# science_pcb_urc_v1.net
KiCad netlist of a schematic drawn in EAGLE
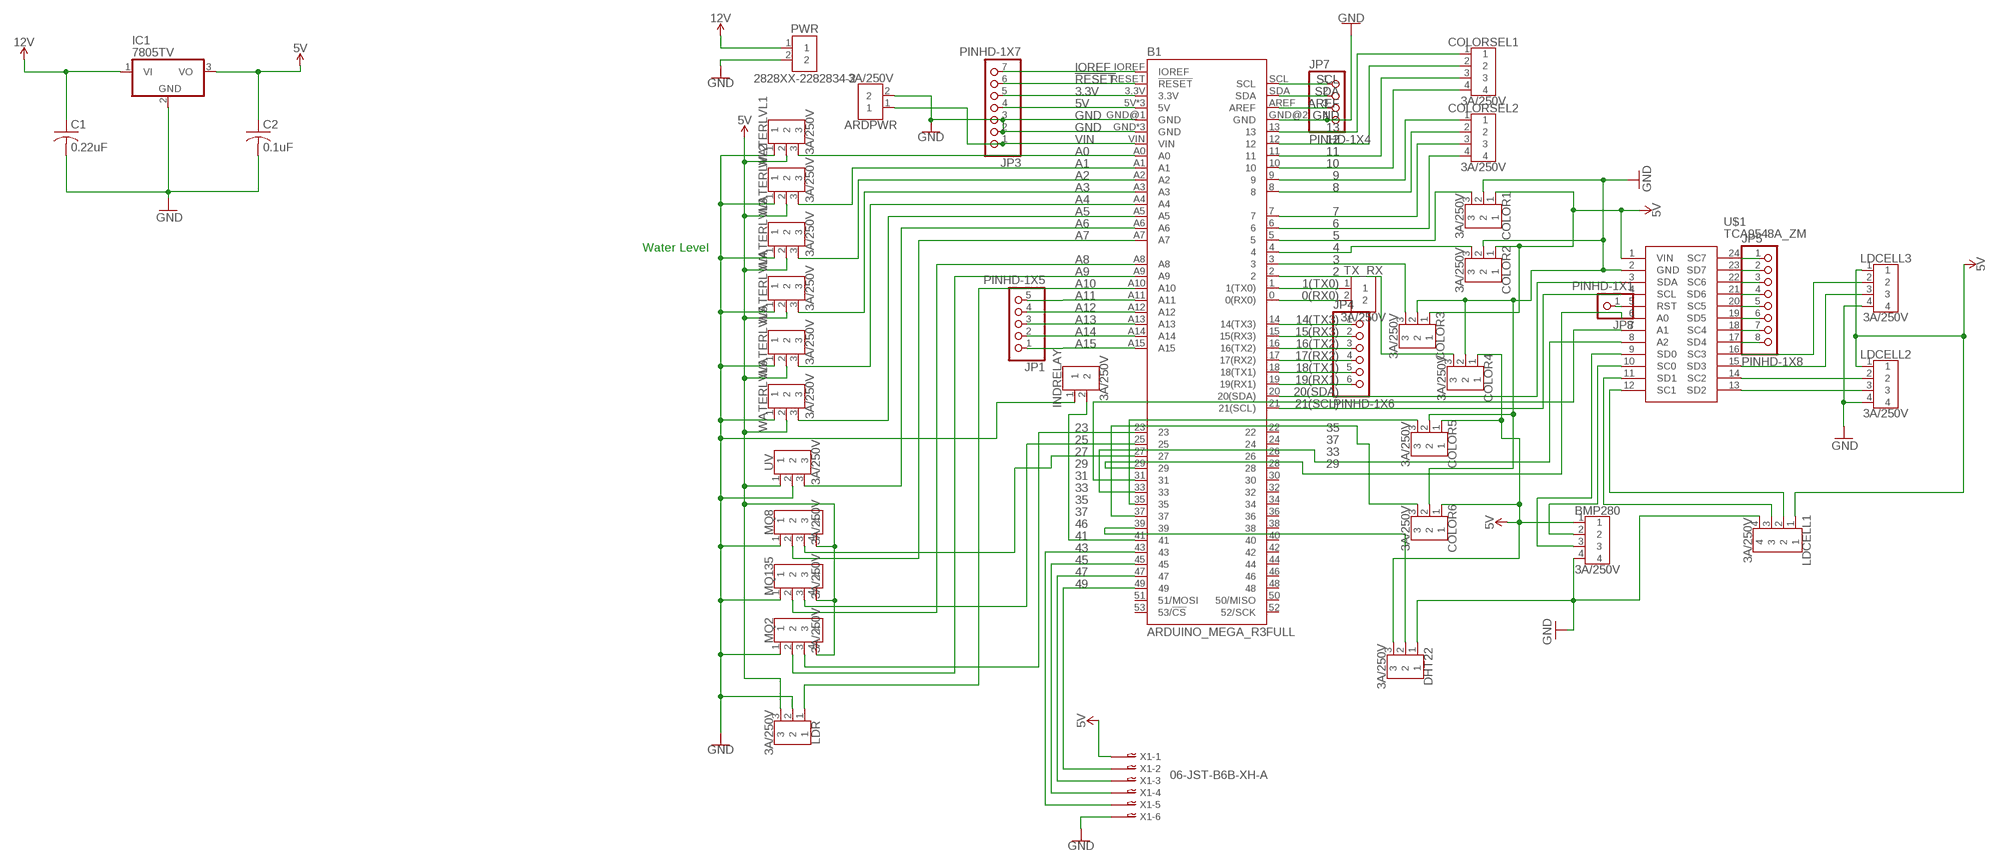
[diagram p0: schematic, sheet 1]

(export (version "E")
  (design (tool "Eeschema 10.0.6"))
  (components
    (comp (ref "ARDPWR")
      (value "3A/250V")
      (footprint "eagle-import:B2B-XH-A")
      (fields (field (name "MANUFACTURER") "JST (XH CONNECTOR)") (field (name "MPN") "B2B-XH-A"))
      (libsource (lib "eagle-import") (part "B2B-XH-A"))
    )
    (comp (ref "B1")
      (value "ARDUINO_MEGA_R3FULL")
      (footprint "eagle-import:ARDUINO_MEGA_NO_SILK")
      (libsource (lib "eagle-import") (part "ARDUINO_MEGA_R3FULL"))
    )
    (comp (ref "BMP280")
      (value "3A/250V")
      (footprint "eagle-import:B4B-XH-A")
      (fields (field (name "MANUFACTURER") "JST (XH connector)") (field (name "MPN") "B4B-XH-A"))
      (libsource (lib "eagle-import") (part "B4B-XH-A"))
    )
    (comp (ref "C1")
      (value "0.22uF")
      (footprint "eagle-import:C025-025X050")
      (libsource (lib "eagle-import") (part "C-US025-025X050"))
    )
    (comp (ref "C2")
      (value "0.1uF")
      (footprint "eagle-import:C025-025X050")
      (libsource (lib "eagle-import") (part "C-US025-025X050"))
    )
    (comp (ref "COLOR1")
      (value "3A/250V")
      (footprint "eagle-import:B3B-XH-A")
      (fields (field (name "MANUFACTURER") "JST (XH connector)") (field (name "MPN") "B3B-XH-A"))
      (libsource (lib "eagle-import") (part "B3B-XH-A"))
    )
    (comp (ref "COLOR2")
      (value "3A/250V")
      (footprint "eagle-import:B3B-XH-A")
      (fields (field (name "MANUFACTURER") "JST (XH connector)") (field (name "MPN") "B3B-XH-A"))
      (libsource (lib "eagle-import") (part "B3B-XH-A"))
    )
    (comp (ref "COLOR3")
      (value "3A/250V")
      (footprint "eagle-import:B3B-XH-A")
      (fields (field (name "MANUFACTURER") "JST (XH connector)") (field (name "MPN") "B3B-XH-A"))
      (libsource (lib "eagle-import") (part "B3B-XH-A"))
    )
    (comp (ref "COLOR4")
      (value "3A/250V")
      (footprint "eagle-import:B3B-XH-A")
      (fields (field (name "MANUFACTURER") "JST (XH connector)") (field (name "MPN") "B3B-XH-A"))
      (libsource (lib "eagle-import") (part "B3B-XH-A"))
    )
    (comp (ref "COLOR5")
      (value "3A/250V")
      (footprint "eagle-import:B3B-XH-A")
      (fields (field (name "MANUFACTURER") "JST (XH connector)") (field (name "MPN") "B3B-XH-A"))
      (libsource (lib "eagle-import") (part "B3B-XH-A"))
    )
    (comp (ref "COLOR6")
      (value "3A/250V")
      (footprint "eagle-import:B3B-XH-A")
      (fields (field (name "MANUFACTURER") "JST (XH connector)") (field (name "MPN") "B3B-XH-A"))
      (libsource (lib "eagle-import") (part "B3B-XH-A"))
    )
    (comp (ref "COLORSEL1")
      (value "3A/250V")
      (footprint "eagle-import:B4B-XH-A")
      (fields (field (name "MANUFACTURER") "JST (XH connector)") (field (name "MPN") "B4B-XH-A"))
      (libsource (lib "eagle-import") (part "B4B-XH-A"))
    )
    (comp (ref "COLORSEL2")
      (value "3A/250V")
      (footprint "eagle-import:B4B-XH-A")
      (fields (field (name "MANUFACTURER") "JST (XH connector)") (field (name "MPN") "B4B-XH-A"))
      (libsource (lib "eagle-import") (part "B4B-XH-A"))
    )
    (comp (ref "DHT22")
      (value "3A/250V")
      (footprint "eagle-import:B3B-XH-A")
      (fields (field (name "MANUFACTURER") "JST (XH connector)") (field (name "MPN") "B3B-XH-A"))
      (libsource (lib "eagle-import") (part "B3B-XH-A"))
    )
    (comp (ref "IC1")
      (value "7805TV")
      (footprint "eagle-import:TO220V")
      (libsource (lib "eagle-import") (part "78TV05"))
    )
    (comp (ref "INDRELAY")
      (value "3A/250V")
      (footprint "eagle-import:B2B-XH-A")
      (fields (field (name "MANUFACTURER") "JST (XH CONNECTOR)") (field (name "MPN") "B2B-XH-A"))
      (libsource (lib "eagle-import") (part "B2B-XH-A"))
    )
    (comp (ref "JP1")
      (value "PINHD-1X5")
      (footprint "eagle-import:1X05")
      (libsource (lib "eagle-import") (part "PINHD-1X5"))
    )
    (comp (ref "JP3")
      (value "PINHD-1X7")
      (footprint "eagle-import:1X07")
      (libsource (lib "eagle-import") (part "PINHD-1X7"))
    )
    (comp (ref "JP4")
      (value "PINHD-1X6")
      (footprint "eagle-import:1X06")
      (libsource (lib "eagle-import") (part "PINHD-1X6"))
    )
    (comp (ref "JP5")
      (value "PINHD-1X8")
      (footprint "eagle-import:1X08")
      (libsource (lib "eagle-import") (part "PINHD-1X8"))
    )
    (comp (ref "JP7")
      (value "PINHD-1X4")
      (footprint "eagle-import:1X04")
      (libsource (lib "eagle-import") (part "PINHD-1X4"))
    )
    (comp (ref "JP8")
      (value "PINHD-1X1")
      (footprint "eagle-import:1X01")
      (libsource (lib "eagle-import") (part "PINHD-1X1"))
    )
    (comp (ref "LDCELL1")
      (value "3A/250V")
      (footprint "eagle-import:B4B-XH-A")
      (fields (field (name "MANUFACTURER") "JST (XH connector)") (field (name "MPN") "B4B-XH-A"))
      (libsource (lib "eagle-import") (part "B4B-XH-A"))
    )
    (comp (ref "LDCELL2")
      (value "3A/250V")
      (footprint "eagle-import:B4B-XH-A")
      (fields (field (name "MANUFACTURER") "JST (XH connector)") (field (name "MPN") "B4B-XH-A"))
      (libsource (lib "eagle-import") (part "B4B-XH-A"))
    )
    (comp (ref "LDCELL3")
      (value "3A/250V")
      (footprint "eagle-import:B4B-XH-A")
      (fields (field (name "MANUFACTURER") "JST (XH connector)") (field (name "MPN") "B4B-XH-A"))
      (libsource (lib "eagle-import") (part "B4B-XH-A"))
    )
    (comp (ref "LDR")
      (value "3A/250V")
      (footprint "eagle-import:B3B-XH-A")
      (fields (field (name "MANUFACTURER") "JST (XH connector)") (field (name "MPN") "B3B-XH-A"))
      (libsource (lib "eagle-import") (part "B3B-XH-A"))
    )
    (comp (ref "MQ2")
      (value "3A/250V")
      (footprint "eagle-import:B4B-XH-A")
      (fields (field (name "MANUFACTURER") "JST (XH connector)") (field (name "MPN") "B4B-XH-A"))
      (libsource (lib "eagle-import") (part "B4B-XH-A"))
    )
    (comp (ref "MQ8")
      (value "3A/250V")
      (footprint "eagle-import:B4B-XH-A")
      (fields (field (name "MANUFACTURER") "JST (XH connector)") (field (name "MPN") "B4B-XH-A"))
      (libsource (lib "eagle-import") (part "B4B-XH-A"))
    )
    (comp (ref "MQ135")
      (value "3A/250V")
      (footprint "eagle-import:B4B-XH-A")
      (fields (field (name "MANUFACTURER") "JST (XH connector)") (field (name "MPN") "B4B-XH-A"))
      (libsource (lib "eagle-import") (part "B4B-XH-A"))
    )
    (comp (ref "PWR")
      (value "2828XX-2282834-2")
      (footprint "eagle-import:TERMBLK_254-2N")
      (libsource (lib "eagle-import") (part "2828XX-2282834-2"))
    )
    (comp (ref "TX_RX")
      (value "3A/250V")
      (footprint "eagle-import:B2B-XH-A")
      (fields (field (name "MANUFACTURER") "JST (XH CONNECTOR)") (field (name "MPN") "B2B-XH-A"))
      (libsource (lib "eagle-import") (part "B2B-XH-A"))
    )
    (comp (ref "U$1")
      (value "TCA9548A_ZM")
      (footprint "eagle-import:2717")
      (libsource (lib "eagle-import") (part "TCA9548A_ZM"))
    )
    (comp (ref "UV")
      (value "3A/250V")
      (footprint "eagle-import:B3B-XH-A")
      (fields (field (name "MANUFACTURER") "JST (XH connector)") (field (name "MPN") "B3B-XH-A"))
      (libsource (lib "eagle-import") (part "B3B-XH-A"))
    )
    (comp (ref "WATERLVL1")
      (value "3A/250V")
      (footprint "eagle-import:B3B-XH-A")
      (fields (field (name "MANUFACTURER") "JST (XH connector)") (field (name "MPN") "B3B-XH-A"))
      (libsource (lib "eagle-import") (part "B3B-XH-A"))
    )
    (comp (ref "WATERLVL2")
      (value "3A/250V")
      (footprint "eagle-import:B3B-XH-A")
      (fields (field (name "MANUFACTURER") "JST (XH connector)") (field (name "MPN") "B3B-XH-A"))
      (libsource (lib "eagle-import") (part "B3B-XH-A"))
    )
    (comp (ref "WATERLVL3")
      (value "3A/250V")
      (footprint "eagle-import:B3B-XH-A")
      (fields (field (name "MANUFACTURER") "JST (XH connector)") (field (name "MPN") "B3B-XH-A"))
      (libsource (lib "eagle-import") (part "B3B-XH-A"))
    )
    (comp (ref "WATERLVL4")
      (value "3A/250V")
      (footprint "eagle-import:B3B-XH-A")
      (fields (field (name "MANUFACTURER") "JST (XH connector)") (field (name "MPN") "B3B-XH-A"))
      (libsource (lib "eagle-import") (part "B3B-XH-A"))
    )
    (comp (ref "WATERLVL5")
      (value "3A/250V")
      (footprint "eagle-import:B3B-XH-A")
      (fields (field (name "MANUFACTURER") "JST (XH connector)") (field (name "MPN") "B3B-XH-A"))
      (libsource (lib "eagle-import") (part "B3B-XH-A"))
    )
    (comp (ref "WATERLVL6")
      (value "3A/250V")
      (footprint "eagle-import:B3B-XH-A")
      (fields (field (name "MANUFACTURER") "JST (XH connector)") (field (name "MPN") "B3B-XH-A"))
      (libsource (lib "eagle-import") (part "B3B-XH-A"))
    )
    (comp (ref "X1")
      (value "06-JST-B6B-XH-A")
      (footprint "eagle-import:B6B-XH")
      (libsource (lib "eagle-import") (part "06-JST-B6B-XH-A"))
    )
  )
  (nets
    (net (code "1") (name "/0(RX0)") (class "Default")
      (node (ref "B1") (pin "0") (pinfunction "0(RX0)_0") (pintype "bidirectional"))
      (node (ref "TX_RX") (pin "2") (pinfunction "2_2") (pintype "bidirectional"))
    )
    (net (code "2") (name "/1(TX0)") (class "Default")
      (node (ref "B1") (pin "1") (pinfunction "1(TX0)_1") (pintype "bidirectional"))
      (node (ref "TX_RX") (pin "1") (pinfunction "1_1") (pintype "bidirectional"))
    )
    (net (code "3") (name "/2") (class "Default")
      (node (ref "B1") (pin "2") (pinfunction "2_2") (pintype "bidirectional"))
      (node (ref "COLOR4") (pin "3") (pinfunction "3_3") (pintype "bidirectional"))
    )
    (net (code "4") (name "/3") (class "Default")
      (node (ref "B1") (pin "3") (pinfunction "3_3") (pintype "bidirectional"))
      (node (ref "COLOR3") (pin "3") (pinfunction "3_3") (pintype "bidirectional"))
    )
    (net (code "5") (name "/3.3V") (class "Default")
      (node (ref "B1") (pin "3.3V") (pinfunction "3.3V_3.3V") (pintype "bidirectional"))
      (node (ref "JP3") (pin "5") (pinfunction "5_5") (pintype "passive"))
    )
    (net (code "6") (name "/4") (class "Default")
      (node (ref "B1") (pin "4") (pinfunction "4_4") (pintype "bidirectional"))
      (node (ref "COLOR2") (pin "3") (pinfunction "3_3") (pintype "bidirectional"))
    )
    (net (code "7") (name "/5") (class "Default")
      (node (ref "B1") (pin "5") (pinfunction "5_5") (pintype "bidirectional"))
      (node (ref "COLOR1") (pin "3") (pinfunction "3_3") (pintype "bidirectional"))
    )
    (net (code "8") (name "/6") (class "Default")
      (node (ref "B1") (pin "6") (pinfunction "6_6") (pintype "bidirectional"))
      (node (ref "COLORSEL2") (pin "4") (pinfunction "4_4") (pintype "bidirectional"))
    )
    (net (code "9") (name "/7") (class "Default")
      (node (ref "B1") (pin "7") (pinfunction "7_7") (pintype "bidirectional"))
      (node (ref "COLORSEL2") (pin "3") (pinfunction "3_3") (pintype "bidirectional"))
    )
    (net (code "10") (name "/8") (class "Default")
      (node (ref "B1") (pin "8") (pinfunction "8_8") (pintype "bidirectional"))
      (node (ref "COLORSEL2") (pin "2") (pinfunction "2_2") (pintype "bidirectional"))
    )
    (net (code "11") (name "/9") (class "Default")
      (node (ref "B1") (pin "9") (pinfunction "9_9") (pintype "bidirectional"))
      (node (ref "COLORSEL2") (pin "1") (pinfunction "1_1") (pintype "bidirectional"))
    )
    (net (code "12") (name "/10") (class "Default")
      (node (ref "B1") (pin "10") (pinfunction "10_10") (pintype "bidirectional"))
      (node (ref "COLORSEL1") (pin "4") (pinfunction "4_4") (pintype "bidirectional"))
    )
    (net (code "13") (name "/11") (class "Default")
      (node (ref "B1") (pin "11") (pinfunction "11_11") (pintype "bidirectional"))
      (node (ref "COLORSEL1") (pin "3") (pinfunction "3_3") (pintype "bidirectional"))
    )
    (net (code "14") (name "/12") (class "Default")
      (node (ref "B1") (pin "12") (pinfunction "12_12") (pintype "bidirectional"))
      (node (ref "COLORSEL1") (pin "2") (pinfunction "2_2") (pintype "bidirectional"))
    )
    (net (code "15") (name "/13") (class "Default")
      (node (ref "B1") (pin "13") (pinfunction "13_13") (pintype "bidirectional"))
      (node (ref "COLORSEL1") (pin "1") (pinfunction "1_1") (pintype "bidirectional"))
    )
    (net (code "16") (name "/14(TX3)") (class "Default")
      (node (ref "B1") (pin "14") (pinfunction "14(TX3)_14") (pintype "bidirectional"))
      (node (ref "JP4") (pin "1") (pinfunction "1_1") (pintype "passive"))
    )
    (net (code "17") (name "/15(RX3)") (class "Default")
      (node (ref "B1") (pin "15") (pinfunction "15(RX3)_15") (pintype "bidirectional"))
      (node (ref "JP4") (pin "2") (pinfunction "2_2") (pintype "passive"))
    )
    (net (code "18") (name "/16(TX2)") (class "Default")
      (node (ref "B1") (pin "16") (pinfunction "16(TX2)_16") (pintype "bidirectional"))
      (node (ref "JP4") (pin "3") (pinfunction "3_3") (pintype "passive"))
    )
    (net (code "19") (name "/17(RX2)") (class "Default")
      (node (ref "B1") (pin "17") (pinfunction "17(RX2)_17") (pintype "bidirectional"))
      (node (ref "JP4") (pin "4") (pinfunction "4_4") (pintype "passive"))
    )
    (net (code "20") (name "/18(TX1)") (class "Default")
      (node (ref "B1") (pin "18") (pinfunction "18(TX1)_18") (pintype "bidirectional"))
      (node (ref "JP4") (pin "5") (pinfunction "5_5") (pintype "passive"))
    )
    (net (code "21") (name "/19(RX1)") (class "Default")
      (node (ref "B1") (pin "19") (pinfunction "19(RX1)_19") (pintype "bidirectional"))
      (node (ref "JP4") (pin "6") (pinfunction "6_6") (pintype "passive"))
    )
    (net (code "22") (name "/20(SDA)") (class "Default")
      (node (ref "B1") (pin "20") (pinfunction "20(SDA)_20") (pintype "bidirectional"))
      (node (ref "U$1") (pin "3") (pinfunction "SDA_3") (pintype "bidirectional"))
    )
    (net (code "23") (name "/21(SCL)") (class "Default")
      (node (ref "B1") (pin "21") (pinfunction "21(SCL)_21") (pintype "bidirectional"))
      (node (ref "U$1") (pin "4") (pinfunction "SCL_4") (pintype "bidirectional"))
    )
    (net (code "24") (name "/23") (class "Default")
      (node (ref "B1") (pin "27") (pinfunction "27_27") (pintype "bidirectional"))
      (node (ref "MQ8") (pin "3") (pinfunction "3_3") (pintype "bidirectional"))
    )
    (net (code "25") (name "/25") (class "Default")
      (node (ref "B1") (pin "25") (pinfunction "25_25") (pintype "bidirectional"))
      (node (ref "MQ135") (pin "3") (pinfunction "3_3") (pintype "bidirectional"))
    )
    (net (code "26") (name "/27") (class "Default")
      (node (ref "B1") (pin "23") (pinfunction "23_23") (pintype "bidirectional"))
      (node (ref "MQ2") (pin "3") (pinfunction "3_3") (pintype "bidirectional"))
    )
    (net (code "27") (name "/29") (class "Default")
      (node (ref "B1") (pin "29") (pinfunction "29_29") (pintype "bidirectional"))
      (node (ref "U$1") (pin "6") (pinfunction "A0_6") (pintype "bidirectional"))
    )
    (net (code "28") (name "/31") (class "Default")
      (node (ref "B1") (pin "31") (pinfunction "31_31") (pintype "bidirectional"))
      (node (ref "U$1") (pin "7") (pinfunction "A1_7") (pintype "bidirectional"))
    )
    (net (code "29") (name "/33") (class "Default")
      (node (ref "B1") (pin "33") (pinfunction "33_33") (pintype "bidirectional"))
      (node (ref "U$1") (pin "8") (pinfunction "A2_8") (pintype "bidirectional"))
    )
    (net (code "30") (name "/35") (class "Default")
      (node (ref "B1") (pin "35") (pinfunction "35_35") (pintype "bidirectional"))
      (node (ref "COLOR5") (pin "3") (pinfunction "3_3") (pintype "bidirectional"))
    )
    (net (code "31") (name "/37") (class "Default")
      (node (ref "B1") (pin "37") (pinfunction "37_37") (pintype "bidirectional"))
      (node (ref "COLOR6") (pin "3") (pinfunction "3_3") (pintype "bidirectional"))
    )
    (net (code "32") (name "/41") (class "Default")
      (node (ref "B1") (pin "41") (pinfunction "41_41") (pintype "bidirectional"))
      (node (ref "INDRELAY") (pin "2") (pinfunction "2_2") (pintype "bidirectional"))
    )
    (net (code "33") (name "/43") (class "Default")
      (node (ref "B1") (pin "43") (pinfunction "43_43") (pintype "bidirectional"))
      (node (ref "X1") (pin "P$5") (pinfunction "1_P$5") (pintype "passive"))
    )
    (net (code "34") (name "/45") (class "Default")
      (node (ref "B1") (pin "45") (pinfunction "45_45") (pintype "bidirectional"))
      (node (ref "X1") (pin "P$4") (pinfunction "1_P$4") (pintype "passive"))
    )
    (net (code "35") (name "/46") (class "Default")
      (node (ref "B1") (pin "39") (pinfunction "39_39") (pintype "bidirectional"))
      (node (ref "DHT22") (pin "2") (pinfunction "2_2") (pintype "bidirectional"))
    )
    (net (code "36") (name "/47") (class "Default")
      (node (ref "B1") (pin "47") (pinfunction "47_47") (pintype "bidirectional"))
      (node (ref "X1") (pin "P$3") (pinfunction "1_P$3") (pintype "passive"))
    )
    (net (code "37") (name "/49") (class "Default")
      (node (ref "B1") (pin "49") (pinfunction "49_49") (pintype "bidirectional"))
      (node (ref "X1") (pin "P$2") (pinfunction "1_P$2") (pintype "passive"))
    )
    (net (code "38") (name "/A0") (class "Default")
      (node (ref "B1") (pin "A0") (pinfunction "A0_A0") (pintype "bidirectional"))
      (node (ref "WATERLVL1") (pin "3") (pinfunction "3_3") (pintype "bidirectional"))
    )
    (net (code "39") (name "/A1") (class "Default")
      (node (ref "B1") (pin "A1") (pinfunction "A1_A1") (pintype "bidirectional"))
      (node (ref "WATERLVL2") (pin "3") (pinfunction "3_3") (pintype "bidirectional"))
    )
    (net (code "40") (name "/A2") (class "Default")
      (node (ref "B1") (pin "A2") (pinfunction "A2_A2") (pintype "bidirectional"))
      (node (ref "WATERLVL3") (pin "3") (pinfunction "3_3") (pintype "bidirectional"))
    )
    (net (code "41") (name "/A3") (class "Default")
      (node (ref "B1") (pin "A3") (pinfunction "A3_A3") (pintype "bidirectional"))
      (node (ref "WATERLVL4") (pin "3") (pinfunction "3_3") (pintype "bidirectional"))
    )
    (net (code "42") (name "/A4") (class "Default")
      (node (ref "B1") (pin "A4") (pinfunction "A4_A4") (pintype "bidirectional"))
      (node (ref "WATERLVL5") (pin "3") (pinfunction "3_3") (pintype "bidirectional"))
    )
    (net (code "43") (name "/A5") (class "Default")
      (node (ref "B1") (pin "A5") (pinfunction "A5_A5") (pintype "bidirectional"))
      (node (ref "WATERLVL6") (pin "3") (pinfunction "3_3") (pintype "bidirectional"))
    )
    (net (code "44") (name "/A6") (class "Default")
      (node (ref "B1") (pin "A6") (pinfunction "A6_A6") (pintype "bidirectional"))
      (node (ref "UV") (pin "3") (pinfunction "3_3") (pintype "bidirectional"))
    )
    (net (code "45") (name "/A7") (class "Default")
      (node (ref "B1") (pin "A7") (pinfunction "A7_A7") (pintype "bidirectional"))
      (node (ref "MQ8") (pin "2") (pinfunction "2_2") (pintype "bidirectional"))
    )
    (net (code "46") (name "/A8") (class "Default")
      (node (ref "B1") (pin "A8") (pinfunction "A8_A8") (pintype "bidirectional"))
      (node (ref "MQ135") (pin "2") (pinfunction "2_2") (pintype "bidirectional"))
    )
    (net (code "47") (name "/A9") (class "Default")
      (node (ref "B1") (pin "A9") (pinfunction "A9_A9") (pintype "bidirectional"))
      (node (ref "MQ2") (pin "2") (pinfunction "2_2") (pintype "bidirectional"))
    )
    (net (code "48") (name "/A10") (class "Default")
      (node (ref "B1") (pin "A10") (pinfunction "A10_A10") (pintype "bidirectional"))
      (node (ref "LDR") (pin "1") (pinfunction "1_1") (pintype "bidirectional"))
    )
    (net (code "49") (name "/A11") (class "Default")
      (node (ref "B1") (pin "A11") (pinfunction "A11_A11") (pintype "bidirectional"))
      (node (ref "JP1") (pin "5") (pinfunction "5_5") (pintype "passive"))
    )
    (net (code "50") (name "/A12") (class "Default")
      (node (ref "B1") (pin "A12") (pinfunction "A12_A12") (pintype "bidirectional"))
      (node (ref "JP1") (pin "4") (pinfunction "4_4") (pintype "passive"))
    )
    (net (code "51") (name "/A13") (class "Default")
      (node (ref "B1") (pin "A13") (pinfunction "A13_A13") (pintype "bidirectional"))
      (node (ref "JP1") (pin "3") (pinfunction "3_3") (pintype "passive"))
    )
    (net (code "52") (name "/A14") (class "Default")
      (node (ref "B1") (pin "A14") (pinfunction "A14_A14") (pintype "bidirectional"))
      (node (ref "JP1") (pin "2") (pinfunction "2_2") (pintype "passive"))
    )
    (net (code "53") (name "/A15") (class "Default")
      (node (ref "B1") (pin "A15") (pinfunction "A15_A15") (pintype "bidirectional"))
      (node (ref "JP1") (pin "1") (pinfunction "1_1") (pintype "passive"))
    )
    (net (code "54") (name "/AREF") (class "Default")
      (node (ref "B1") (pin "AREF") (pinfunction "AREF_AREF") (pintype "bidirectional"))
      (node (ref "JP7") (pin "3") (pinfunction "3_3") (pintype "passive"))
    )
    (net (code "55") (name "/IOREF") (class "Default")
      (node (ref "B1") (pin "IOREF") (pinfunction "IOREF_IOREF") (pintype "bidirectional"))
      (node (ref "JP3") (pin "7") (pinfunction "7_7") (pintype "passive"))
    )
    (net (code "56") (name "/SCL") (class "Default")
      (node (ref "B1") (pin "SCL") (pinfunction "SCL_SCL") (pintype "bidirectional"))
      (node (ref "JP7") (pin "1") (pinfunction "1_1") (pintype "passive"))
    )
    (net (code "57") (name "/SDA") (class "Default")
      (node (ref "B1") (pin "SDA") (pinfunction "SDA_SDA") (pintype "bidirectional"))
      (node (ref "JP7") (pin "2") (pinfunction "2_2") (pintype "passive"))
    )
    (net (code "58") (name "/VIN") (class "Default")
      (node (ref "ARDPWR") (pin "1") (pinfunction "1_1") (pintype "bidirectional"))
      (node (ref "B1") (pin "VIN") (pinfunction "VIN_VIN") (pintype "bidirectional"))
      (node (ref "JP3") (pin "1") (pinfunction "1_1") (pintype "passive"))
    )
    (net (code "59") (name "/~{RESET}") (class "Default")
      (node (ref "B1") (pin "RESET") (pinfunction "~{RESET}_RESET") (pintype "bidirectional"))
      (node (ref "JP3") (pin "6") (pinfunction "6_6") (pintype "passive"))
    )
    (net (code "60") (name "5V") (class "Default")
      (node (ref "B1") (pin "5V") (pinfunction "5V_5V") (pintype "bidirectional"))
      (node (ref "B1") (pin "5V@1") (pinfunction "5V_5V@1") (pintype "bidirectional"))
      (node (ref "B1") (pin "5V@2") (pinfunction "5V_5V@2") (pintype "bidirectional"))
      (node (ref "BMP280") (pin "1") (pinfunction "1_1") (pintype "bidirectional"))
      (node (ref "C2") (pin "1") (pinfunction "1_1") (pintype "passive"))
      (node (ref "COLOR1") (pin "1") (pinfunction "1_1") (pintype "bidirectional"))
      (node (ref "COLOR2") (pin "1") (pinfunction "1_1") (pintype "bidirectional"))
      (node (ref "COLOR3") (pin "1") (pinfunction "1_1") (pintype "bidirectional"))
      (node (ref "COLOR4") (pin "1") (pinfunction "1_1") (pintype "bidirectional"))
      (node (ref "COLOR5") (pin "1") (pinfunction "1_1") (pintype "bidirectional"))
      (node (ref "COLOR6") (pin "1") (pinfunction "1_1") (pintype "bidirectional"))
      (node (ref "DHT22") (pin "3") (pinfunction "3_3") (pintype "bidirectional"))
      (node (ref "IC1") (pin "3") (pinfunction "VO_3") (pintype "passive"))
      (node (ref "JP3") (pin "4") (pinfunction "4_4") (pintype "passive"))
      (node (ref "LDCELL1") (pin "1") (pinfunction "1_1") (pintype "bidirectional"))
      (node (ref "LDCELL2") (pin "1") (pinfunction "1_1") (pintype "bidirectional"))
      (node (ref "LDCELL3") (pin "1") (pinfunction "1_1") (pintype "bidirectional"))
      (node (ref "LDR") (pin "3") (pinfunction "3_3") (pintype "bidirectional"))
      (node (ref "MQ135") (pin "4") (pinfunction "4_4") (pintype "bidirectional"))
      (node (ref "MQ2") (pin "4") (pinfunction "4_4") (pintype "bidirectional"))
      (node (ref "MQ8") (pin "4") (pinfunction "4_4") (pintype "bidirectional"))
      (node (ref "U$1") (pin "1") (pinfunction "VIN_1") (pintype "bidirectional"))
      (node (ref "UV") (pin "1") (pinfunction "1_1") (pintype "bidirectional"))
      (node (ref "WATERLVL1") (pin "2") (pinfunction "2_2") (pintype "bidirectional"))
      (node (ref "WATERLVL2") (pin "2") (pinfunction "2_2") (pintype "bidirectional"))
      (node (ref "WATERLVL3") (pin "2") (pinfunction "2_2") (pintype "bidirectional"))
      (node (ref "WATERLVL4") (pin "2") (pinfunction "2_2") (pintype "bidirectional"))
      (node (ref "WATERLVL5") (pin "2") (pinfunction "2_2") (pintype "bidirectional"))
      (node (ref "WATERLVL6") (pin "2") (pinfunction "2_2") (pintype "bidirectional"))
      (node (ref "X1") (pin "P$1") (pinfunction "1_P$1") (pintype "passive"))
    )
    (net (code "61") (name "12V") (class "Default")
      (node (ref "C1") (pin "1") (pinfunction "1_1") (pintype "passive"))
      (node (ref "IC1") (pin "1") (pinfunction "VI_1") (pintype "input"))
      (node (ref "PWR") (pin "1") (pinfunction "1_1") (pintype "bidirectional"))
    )
    (net (code "62") (name "GND") (class "Default")
      (node (ref "ARDPWR") (pin "2") (pinfunction "2_2") (pintype "bidirectional"))
      (node (ref "B1") (pin "GND") (pinfunction "GND_GND") (pintype "bidirectional"))
      (node (ref "B1") (pin "GND@1") (pinfunction "GND_GND@1") (pintype "bidirectional"))
      (node (ref "B1") (pin "GND@2") (pinfunction "GND_GND@2") (pintype "bidirectional"))
      (node (ref "B1") (pin "GND@3") (pinfunction "GND_GND@3") (pintype "bidirectional"))
      (node (ref "B1") (pin "GND@4") (pinfunction "GND_GND@4") (pintype "bidirectional"))
      (node (ref "BMP280") (pin "4") (pinfunction "4_4") (pintype "bidirectional"))
      (node (ref "C1") (pin "2") (pinfunction "2_2") (pintype "passive"))
      (node (ref "C2") (pin "2") (pinfunction "2_2") (pintype "passive"))
      (node (ref "COLOR1") (pin "2") (pinfunction "2_2") (pintype "bidirectional"))
      (node (ref "COLOR2") (pin "2") (pinfunction "2_2") (pintype "bidirectional"))
      (node (ref "COLOR3") (pin "2") (pinfunction "2_2") (pintype "bidirectional"))
      (node (ref "COLOR4") (pin "2") (pinfunction "2_2") (pintype "bidirectional"))
      (node (ref "COLOR5") (pin "2") (pinfunction "2_2") (pintype "bidirectional"))
      (node (ref "COLOR6") (pin "2") (pinfunction "2_2") (pintype "bidirectional"))
      (node (ref "DHT22") (pin "1") (pinfunction "1_1") (pintype "bidirectional"))
      (node (ref "IC1") (pin "2") (pinfunction "GND_2") (pintype "passive"))
      (node (ref "INDRELAY") (pin "1") (pinfunction "1_1") (pintype "bidirectional"))
      (node (ref "JP3") (pin "2") (pinfunction "2_2") (pintype "passive"))
      (node (ref "JP3") (pin "3") (pinfunction "3_3") (pintype "passive"))
      (node (ref "JP7") (pin "4") (pinfunction "4_4") (pintype "passive"))
      (node (ref "LDCELL1") (pin "4") (pinfunction "4_4") (pintype "bidirectional"))
      (node (ref "LDCELL2") (pin "4") (pinfunction "4_4") (pintype "bidirectional"))
      (node (ref "LDCELL3") (pin "4") (pinfunction "4_4") (pintype "bidirectional"))
      (node (ref "LDR") (pin "2") (pinfunction "2_2") (pintype "bidirectional"))
      (node (ref "MQ135") (pin "1") (pinfunction "1_1") (pintype "bidirectional"))
      (node (ref "MQ2") (pin "1") (pinfunction "1_1") (pintype "bidirectional"))
      (node (ref "MQ8") (pin "1") (pinfunction "1_1") (pintype "bidirectional"))
      (node (ref "PWR") (pin "2") (pinfunction "2_2") (pintype "bidirectional"))
      (node (ref "U$1") (pin "2") (pinfunction "GND_2") (pintype "bidirectional"))
      (node (ref "UV") (pin "2") (pinfunction "2_2") (pintype "bidirectional"))
      (node (ref "WATERLVL1") (pin "1") (pinfunction "1_1") (pintype "bidirectional"))
      (node (ref "WATERLVL2") (pin "1") (pinfunction "1_1") (pintype "bidirectional"))
      (node (ref "WATERLVL3") (pin "1") (pinfunction "1_1") (pintype "bidirectional"))
      (node (ref "WATERLVL4") (pin "1") (pinfunction "1_1") (pintype "bidirectional"))
      (node (ref "WATERLVL5") (pin "1") (pinfunction "1_1") (pintype "bidirectional"))
      (node (ref "WATERLVL6") (pin "1") (pinfunction "1_1") (pintype "bidirectional"))
      (node (ref "X1") (pin "P$6") (pinfunction "1_P$6") (pintype "passive"))
    )
    (net (code "63") (name "Net-(U$1-RST)") (class "Default")
      (node (ref "JP8") (pin "1") (pinfunction "1_1") (pintype "passive"))
      (node (ref "U$1") (pin "5") (pinfunction "RST_5") (pintype "bidirectional"))
    )
    (net (code "64") (name "Net-(U$1-SC0)") (class "Default")
      (node (ref "BMP280") (pin "2") (pinfunction "2_2") (pintype "bidirectional"))
      (node (ref "U$1") (pin "10") (pinfunction "SC0_10") (pintype "bidirectional"))
    )
    (net (code "65") (name "Net-(U$1-SC1)") (class "Default")
      (node (ref "LDCELL1") (pin "2") (pinfunction "2_2") (pintype "bidirectional"))
      (node (ref "U$1") (pin "12") (pinfunction "SC1_12") (pintype "bidirectional"))
    )
    (net (code "66") (name "Net-(U$1-SC2)") (class "Default")
      (node (ref "LDCELL2") (pin "2") (pinfunction "2_2") (pintype "bidirectional"))
      (node (ref "U$1") (pin "14") (pinfunction "SC2_14") (pintype "bidirectional"))
    )
    (net (code "67") (name "Net-(U$1-SC3)") (class "Default")
      (node (ref "LDCELL3") (pin "2") (pinfunction "2_2") (pintype "bidirectional"))
      (node (ref "U$1") (pin "16") (pinfunction "SC3_16") (pintype "bidirectional"))
    )
    (net (code "68") (name "Net-(U$1-SC4)") (class "Default")
      (node (ref "JP5") (pin "7") (pinfunction "7_7") (pintype "passive"))
      (node (ref "U$1") (pin "18") (pinfunction "SC4_18") (pintype "bidirectional"))
    )
    (net (code "69") (name "Net-(U$1-SC5)") (class "Default")
      (node (ref "JP5") (pin "5") (pinfunction "5_5") (pintype "passive"))
      (node (ref "U$1") (pin "20") (pinfunction "SC5_20") (pintype "bidirectional"))
    )
    (net (code "70") (name "Net-(U$1-SC6)") (class "Default")
      (node (ref "JP5") (pin "3") (pinfunction "3_3") (pintype "passive"))
      (node (ref "U$1") (pin "22") (pinfunction "SC6_22") (pintype "bidirectional"))
    )
    (net (code "71") (name "Net-(U$1-SC7)") (class "Default")
      (node (ref "JP5") (pin "1") (pinfunction "1_1") (pintype "passive"))
      (node (ref "U$1") (pin "24") (pinfunction "SC7_24") (pintype "bidirectional"))
    )
    (net (code "72") (name "Net-(U$1-SD0)") (class "Default")
      (node (ref "BMP280") (pin "3") (pinfunction "3_3") (pintype "bidirectional"))
      (node (ref "U$1") (pin "9") (pinfunction "SD0_9") (pintype "bidirectional"))
    )
    (net (code "73") (name "Net-(U$1-SD1)") (class "Default")
      (node (ref "LDCELL1") (pin "3") (pinfunction "3_3") (pintype "bidirectional"))
      (node (ref "U$1") (pin "11") (pinfunction "SD1_11") (pintype "bidirectional"))
    )
    (net (code "74") (name "Net-(U$1-SD2)") (class "Default")
      (node (ref "LDCELL2") (pin "3") (pinfunction "3_3") (pintype "bidirectional"))
      (node (ref "U$1") (pin "13") (pinfunction "SD2_13") (pintype "bidirectional"))
    )
    (net (code "75") (name "Net-(U$1-SD3)") (class "Default")
      (node (ref "LDCELL3") (pin "3") (pinfunction "3_3") (pintype "bidirectional"))
      (node (ref "U$1") (pin "15") (pinfunction "SD3_15") (pintype "bidirectional"))
    )
    (net (code "76") (name "Net-(U$1-SD4)") (class "Default")
      (node (ref "JP5") (pin "8") (pinfunction "8_8") (pintype "passive"))
      (node (ref "U$1") (pin "17") (pinfunction "SD4_17") (pintype "bidirectional"))
    )
    (net (code "77") (name "Net-(U$1-SD5)") (class "Default")
      (node (ref "JP5") (pin "6") (pinfunction "6_6") (pintype "passive"))
      (node (ref "U$1") (pin "19") (pinfunction "SD5_19") (pintype "bidirectional"))
    )
    (net (code "78") (name "Net-(U$1-SD6)") (class "Default")
      (node (ref "JP5") (pin "4") (pinfunction "4_4") (pintype "passive"))
      (node (ref "U$1") (pin "21") (pinfunction "SD6_21") (pintype "bidirectional"))
    )
    (net (code "79") (name "Net-(U$1-SD7)") (class "Default")
      (node (ref "JP5") (pin "2") (pinfunction "2_2") (pintype "passive"))
      (node (ref "U$1") (pin "23") (pinfunction "SD7_23") (pintype "bidirectional"))
    )
    (net (code "80") (name "unconnected-(B1-50{slash}MISO-Pad50)") (class "Default")
      (node (ref "B1") (pin "50") (pinfunction "50/MISO_50") (pintype "bidirectional"))
    )
    (net (code "81") (name "unconnected-(B1-51{slash}MOSI-Pad51)") (class "Default")
      (node (ref "B1") (pin "51") (pinfunction "51/MOSI_51") (pintype "bidirectional"))
    )
    (net (code "82") (name "unconnected-(B1-52{slash}SCK-Pad52)") (class "Default")
      (node (ref "B1") (pin "52") (pinfunction "52/SCK_52") (pintype "bidirectional"))
    )
    (net (code "83") (name "unconnected-(B1-53{slash}~{CS}-Pad53)") (class "Default")
      (node (ref "B1") (pin "53") (pinfunction "53/~{CS}_53") (pintype "bidirectional"))
    )
    (net (code "84") (name "unconnected-(B1-Pad22)") (class "Default")
      (node (ref "B1") (pin "22") (pinfunction "22_22") (pintype "bidirectional"))
    )
    (net (code "85") (name "unconnected-(B1-Pad24)") (class "Default")
      (node (ref "B1") (pin "24") (pinfunction "24_24") (pintype "bidirectional"))
    )
    (net (code "86") (name "unconnected-(B1-Pad26)") (class "Default")
      (node (ref "B1") (pin "26") (pinfunction "26_26") (pintype "bidirectional"))
    )
    (net (code "87") (name "unconnected-(B1-Pad28)") (class "Default")
      (node (ref "B1") (pin "28") (pinfunction "28_28") (pintype "bidirectional"))
    )
    (net (code "88") (name "unconnected-(B1-Pad30)") (class "Default")
      (node (ref "B1") (pin "30") (pinfunction "30_30") (pintype "bidirectional"))
    )
    (net (code "89") (name "unconnected-(B1-Pad32)") (class "Default")
      (node (ref "B1") (pin "32") (pinfunction "32_32") (pintype "bidirectional"))
    )
    (net (code "90") (name "unconnected-(B1-Pad34)") (class "Default")
      (node (ref "B1") (pin "34") (pinfunction "34_34") (pintype "bidirectional"))
    )
    (net (code "91") (name "unconnected-(B1-Pad36)") (class "Default")
      (node (ref "B1") (pin "36") (pinfunction "36_36") (pintype "bidirectional"))
    )
    (net (code "92") (name "unconnected-(B1-Pad38)") (class "Default")
      (node (ref "B1") (pin "38") (pinfunction "38_38") (pintype "bidirectional"))
    )
    (net (code "93") (name "unconnected-(B1-Pad40)") (class "Default")
      (node (ref "B1") (pin "40") (pinfunction "40_40") (pintype "bidirectional"))
    )
    (net (code "94") (name "unconnected-(B1-Pad42)") (class "Default")
      (node (ref "B1") (pin "42") (pinfunction "42_42") (pintype "bidirectional"))
    )
    (net (code "95") (name "unconnected-(B1-Pad44)") (class "Default")
      (node (ref "B1") (pin "44") (pinfunction "44_44") (pintype "bidirectional"))
    )
    (net (code "96") (name "unconnected-(B1-Pad46)") (class "Default")
      (node (ref "B1") (pin "46") (pinfunction "46_46") (pintype "bidirectional"))
    )
    (net (code "97") (name "unconnected-(B1-Pad48)") (class "Default")
      (node (ref "B1") (pin "48") (pinfunction "48_48") (pintype "bidirectional"))
    )
  )
)
